# LCD.net
KiCad netlist of a schematic drawn in Altium Designer
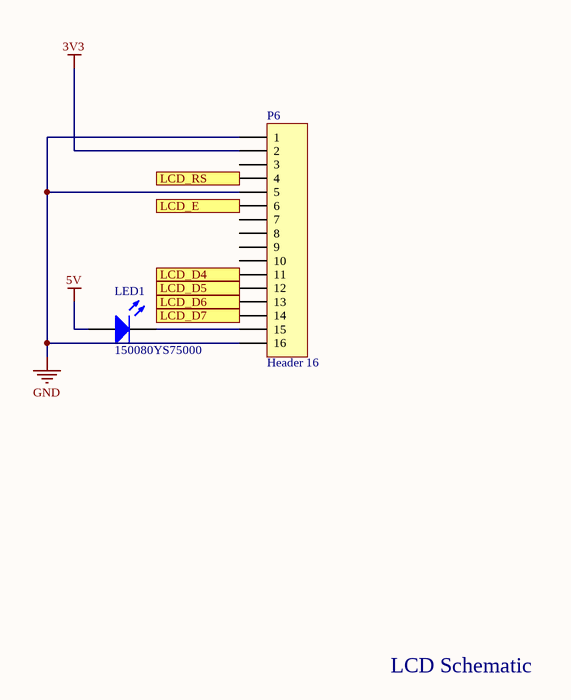
[diagram p0: LCD.SchDoc]

(export (version "E")
  (design (tool "Eeschema 10.0.6"))
  (components
    (comp (ref "LED1")
      (value "150080YS75000")
      (footprint "0805_A")
      (description "SMD mono-color Chip LED, WL-SMCW, Yellow")
      (fields (field (name "MANUFACTURER") "Wuerth Elektronik"))
      (libsource (lib "Altium Content Vault") (part "WE-LED_K1A2-2"))
    )
    (comp (ref "P6")
      (value "Header 16")
      (footprint "HDR1X16")
      (description "Header, 16-Pin")
      (fields (field (name "PUBLISHER") "Altium Limited"))
      (libsource (lib "Miscellaneous Connectors") (part "Header 16"))
    )
  )
  (nets
    (net (code "1") (name "/LCD_D4") (class "Default")
      (node (ref "P6") (pin "11") (pinfunction "11_11") (pintype "passive"))
    )
    (net (code "2") (name "/LCD_D5") (class "Default")
      (node (ref "P6") (pin "12") (pinfunction "12_12") (pintype "passive"))
    )
    (net (code "3") (name "/LCD_D6") (class "Default")
      (node (ref "P6") (pin "13") (pinfunction "13_13") (pintype "passive"))
    )
    (net (code "4") (name "/LCD_D7") (class "Default")
      (node (ref "P6") (pin "14") (pinfunction "14_14") (pintype "passive"))
    )
    (net (code "5") (name "/LCD_E") (class "Default")
      (node (ref "P6") (pin "6") (pinfunction "6_6") (pintype "passive"))
    )
    (net (code "6") (name "/LCD_RS") (class "Default")
      (node (ref "P6") (pin "4") (pinfunction "4_4") (pintype "passive"))
    )
    (net (code "7") (name "3V3") (class "Default")
      (node (ref "P6") (pin "2") (pinfunction "2_2") (pintype "passive"))
    )
    (net (code "8") (name "5V") (class "Default")
      (node (ref "LED1") (pin "2") (pinfunction "A_2") (pintype "passive"))
    )
    (net (code "9") (name "GND") (class "Default")
      (node (ref "P6") (pin "1") (pinfunction "1_1") (pintype "passive"))
      (node (ref "P6") (pin "16") (pinfunction "16_16") (pintype "passive"))
      (node (ref "P6") (pin "5") (pinfunction "5_5") (pintype "passive"))
    )
    (net (code "10") (name "Net-(LED1-K)") (class "Default")
      (node (ref "LED1") (pin "1") (pinfunction "K_1") (pintype "passive"))
      (node (ref "P6") (pin "15") (pinfunction "15_15") (pintype "passive"))
    )
    (net (code "11") (name "unconnected-(P6-Pad3)") (class "Default")
      (node (ref "P6") (pin "3") (pinfunction "3_3") (pintype "passive"))
    )
    (net (code "12") (name "unconnected-(P6-Pad7)") (class "Default")
      (node (ref "P6") (pin "7") (pinfunction "7_7") (pintype "passive"))
    )
    (net (code "13") (name "unconnected-(P6-Pad8)") (class "Default")
      (node (ref "P6") (pin "8") (pinfunction "8_8") (pintype "passive"))
    )
    (net (code "14") (name "unconnected-(P6-Pad9)") (class "Default")
      (node (ref "P6") (pin "9") (pinfunction "9_9") (pintype "passive"))
    )
    (net (code "15") (name "unconnected-(P6-Pad10)") (class "Default")
      (node (ref "P6") (pin "10") (pinfunction "10_10") (pintype "passive"))
    )
  )
)
